# eeZeeAmp.net
KiCad netlist of a schematic drawn in EAGLE
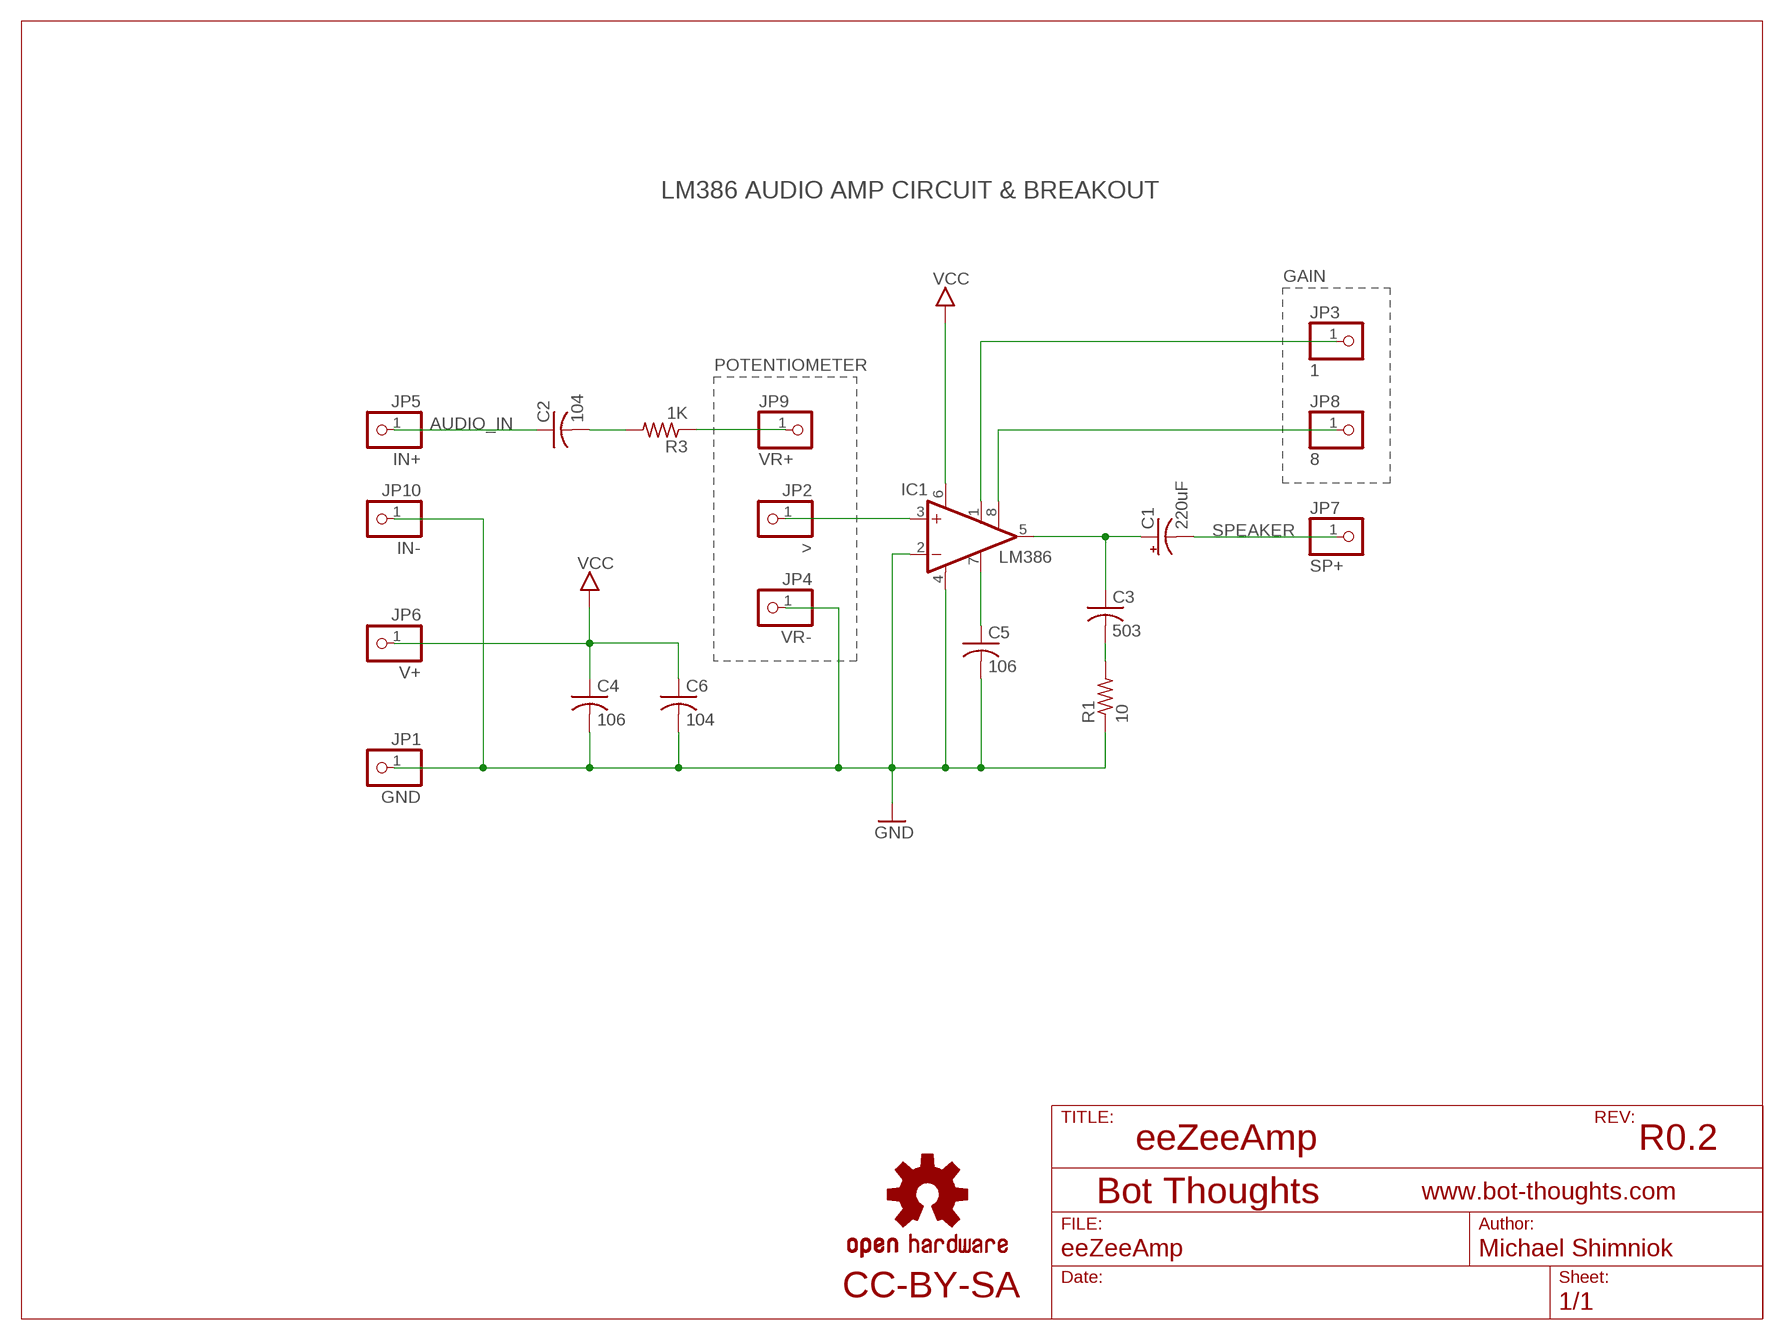
[diagram p0: schematic, sheet 1]

(export (version "E")
  (design (tool "Eeschema 10.0.6"))
  (components
    (comp (ref "C1")
      (value "220uF")
      (footprint "eagle-import:E3,5-8")
      (libsource (lib "eagle-import") (part "CPOL-USE3.5-8"))
    )
    (comp (ref "C2")
      (value "104")
      (footprint "eagle-import:C0603")
      (libsource (lib "eagle-import") (part "C-USC0603"))
    )
    (comp (ref "C3")
      (value "503")
      (footprint "eagle-import:C0603")
      (libsource (lib "eagle-import") (part "C-USC0603"))
    )
    (comp (ref "C4")
      (value "106")
      (footprint "eagle-import:C1206")
      (libsource (lib "eagle-import") (part "C-USC1206"))
    )
    (comp (ref "C5")
      (value "106")
      (footprint "eagle-import:C1206")
      (libsource (lib "eagle-import") (part "C-USC1206"))
    )
    (comp (ref "C6")
      (value "104")
      (footprint "eagle-import:C0603")
      (libsource (lib "eagle-import") (part "C-USC0603"))
    )
    (comp (ref "IC1")
      (value "LM386")
      (footprint "eagle-import:SO08")
      (libsource (lib "eagle-import") (part "LM386?-M1"))
    )
    (comp (ref "JP1")
      (value "GND")
      (footprint "eagle-import:1X01-S")
      (libsource (lib "eagle-import") (part "PINHD-1X01_2.54-S"))
    )
    (comp (ref "JP2")
      (value ">")
      (footprint "eagle-import:1X01-S")
      (libsource (lib "eagle-import") (part "PINHD-1X01_2.54-S"))
    )
    (comp (ref "JP3")
      (value "1")
      (footprint "eagle-import:1X01-S")
      (libsource (lib "eagle-import") (part "PINHD-1X01_2.54-S"))
    )
    (comp (ref "JP4")
      (value "VR-")
      (footprint "eagle-import:1X01-S")
      (libsource (lib "eagle-import") (part "PINHD-1X01_2.54-S"))
    )
    (comp (ref "JP5")
      (value "IN+")
      (footprint "eagle-import:1X01-S")
      (libsource (lib "eagle-import") (part "PINHD-1X01_2.54-S"))
    )
    (comp (ref "JP6")
      (value "V+")
      (footprint "eagle-import:1X01-S")
      (libsource (lib "eagle-import") (part "PINHD-1X01_2.54-S"))
    )
    (comp (ref "JP7")
      (value "SP+")
      (footprint "eagle-import:1X01-S")
      (libsource (lib "eagle-import") (part "PINHD-1X01_2.54-S"))
    )
    (comp (ref "JP8")
      (value "8")
      (footprint "eagle-import:1X01-S")
      (libsource (lib "eagle-import") (part "PINHD-1X01_2.54-S"))
    )
    (comp (ref "JP9")
      (value "VR+")
      (footprint "eagle-import:1X01-S")
      (libsource (lib "eagle-import") (part "PINHD-1X01_2.54-S"))
    )
    (comp (ref "JP10")
      (value "IN-")
      (footprint "eagle-import:1X01-S")
      (libsource (lib "eagle-import") (part "PINHD-1X01_2.54-S"))
    )
    (comp (ref "LOGO2")
      (value "OSHW-LOGOS")
      (footprint "eagle-import:OSHW-LOGO-S")
      (libsource (lib "eagle-import") (part "OSHW-LOGOS"))
    )
    (comp (ref "R1")
      (value "10")
      (footprint "eagle-import:R0603")
      (libsource (lib "eagle-import") (part "R-US_R0603"))
    )
    (comp (ref "R3")
      (value "1K")
      (footprint "eagle-import:R0603")
      (libsource (lib "eagle-import") (part "R-US_R0603"))
    )
  )
  (nets
    (net (code "1") (name "/AUDIO_IN") (class "Default")
      (node (ref "C2") (pin "1") (pinfunction "1_1") (pintype "passive"))
      (node (ref "JP5") (pin "1") (pinfunction "1_1") (pintype "passive"))
    )
    (net (code "2") (name "/SPEAKER") (class "Default")
      (node (ref "C1") (pin "-") (pinfunction "-_-") (pintype "passive"))
      (node (ref "JP7") (pin "1") (pinfunction "1_1") (pintype "passive"))
    )
    (net (code "3") (name "GND") (class "Default")
      (node (ref "C4") (pin "2") (pinfunction "2_2") (pintype "passive"))
      (node (ref "C5") (pin "2") (pinfunction "2_2") (pintype "passive"))
      (node (ref "C6") (pin "2") (pinfunction "2_2") (pintype "passive"))
      (node (ref "IC1") (pin "2") (pinfunction "-IN_2") (pintype "input"))
      (node (ref "IC1") (pin "4") (pinfunction "GND_4") (pintype "power_in"))
      (node (ref "JP1") (pin "1") (pinfunction "1_1") (pintype "passive"))
      (node (ref "JP10") (pin "1") (pinfunction "1_1") (pintype "passive"))
      (node (ref "JP4") (pin "1") (pinfunction "1_1") (pintype "passive"))
      (node (ref "R1") (pin "1") (pinfunction "1_1") (pintype "passive"))
    )
    (net (code "4") (name "Net-(C2-Pad2)") (class "Default")
      (node (ref "C2") (pin "2") (pinfunction "2_2") (pintype "passive"))
      (node (ref "R3") (pin "2") (pinfunction "2_2") (pintype "passive"))
    )
    (net (code "5") (name "Net-(C3-Pad2)") (class "Default")
      (node (ref "C3") (pin "2") (pinfunction "2_2") (pintype "passive"))
      (node (ref "R1") (pin "2") (pinfunction "2_2") (pintype "passive"))
    )
    (net (code "6") (name "Net-(IC1-+IN)") (class "Default")
      (node (ref "IC1") (pin "3") (pinfunction "+IN_3") (pintype "input"))
      (node (ref "JP2") (pin "1") (pinfunction "1_1") (pintype "passive"))
    )
    (net (code "7") (name "Net-(IC1-BYPASS)") (class "Default")
      (node (ref "C5") (pin "1") (pinfunction "1_1") (pintype "passive"))
      (node (ref "IC1") (pin "7") (pinfunction "BYPASS_7") (pintype "passive"))
    )
    (net (code "8") (name "Net-(IC1-GAIN-Pad1)") (class "Default")
      (node (ref "IC1") (pin "1") (pinfunction "GAIN_1") (pintype "passive"))
      (node (ref "JP3") (pin "1") (pinfunction "1_1") (pintype "passive"))
    )
    (net (code "9") (name "Net-(IC1-GAIN-Pad8)") (class "Default")
      (node (ref "IC1") (pin "8") (pinfunction "GAIN_8") (pintype "passive"))
      (node (ref "JP8") (pin "1") (pinfunction "1_1") (pintype "passive"))
    )
    (net (code "10") (name "Net-(IC1-OUT)") (class "Default")
      (node (ref "C1") (pin "+") (pinfunction "+_+") (pintype "passive"))
      (node (ref "C3") (pin "1") (pinfunction "1_1") (pintype "passive"))
      (node (ref "IC1") (pin "5") (pinfunction "OUT_5") (pintype "output"))
    )
    (net (code "11") (name "Net-(JP9-Pad1)") (class "Default")
      (node (ref "JP9") (pin "1") (pinfunction "1_1") (pintype "passive"))
      (node (ref "R3") (pin "1") (pinfunction "1_1") (pintype "passive"))
    )
    (net (code "12") (name "VCC") (class "Default")
      (node (ref "C4") (pin "1") (pinfunction "1_1") (pintype "passive"))
      (node (ref "C6") (pin "1") (pinfunction "1_1") (pintype "passive"))
      (node (ref "IC1") (pin "6") (pinfunction "VS_6") (pintype "power_in"))
      (node (ref "JP6") (pin "1") (pinfunction "1_1") (pintype "passive"))
    )
  )
)
